# VESC_POWER_SCH.net
KiCad netlist of a schematic drawn in Altium Designer
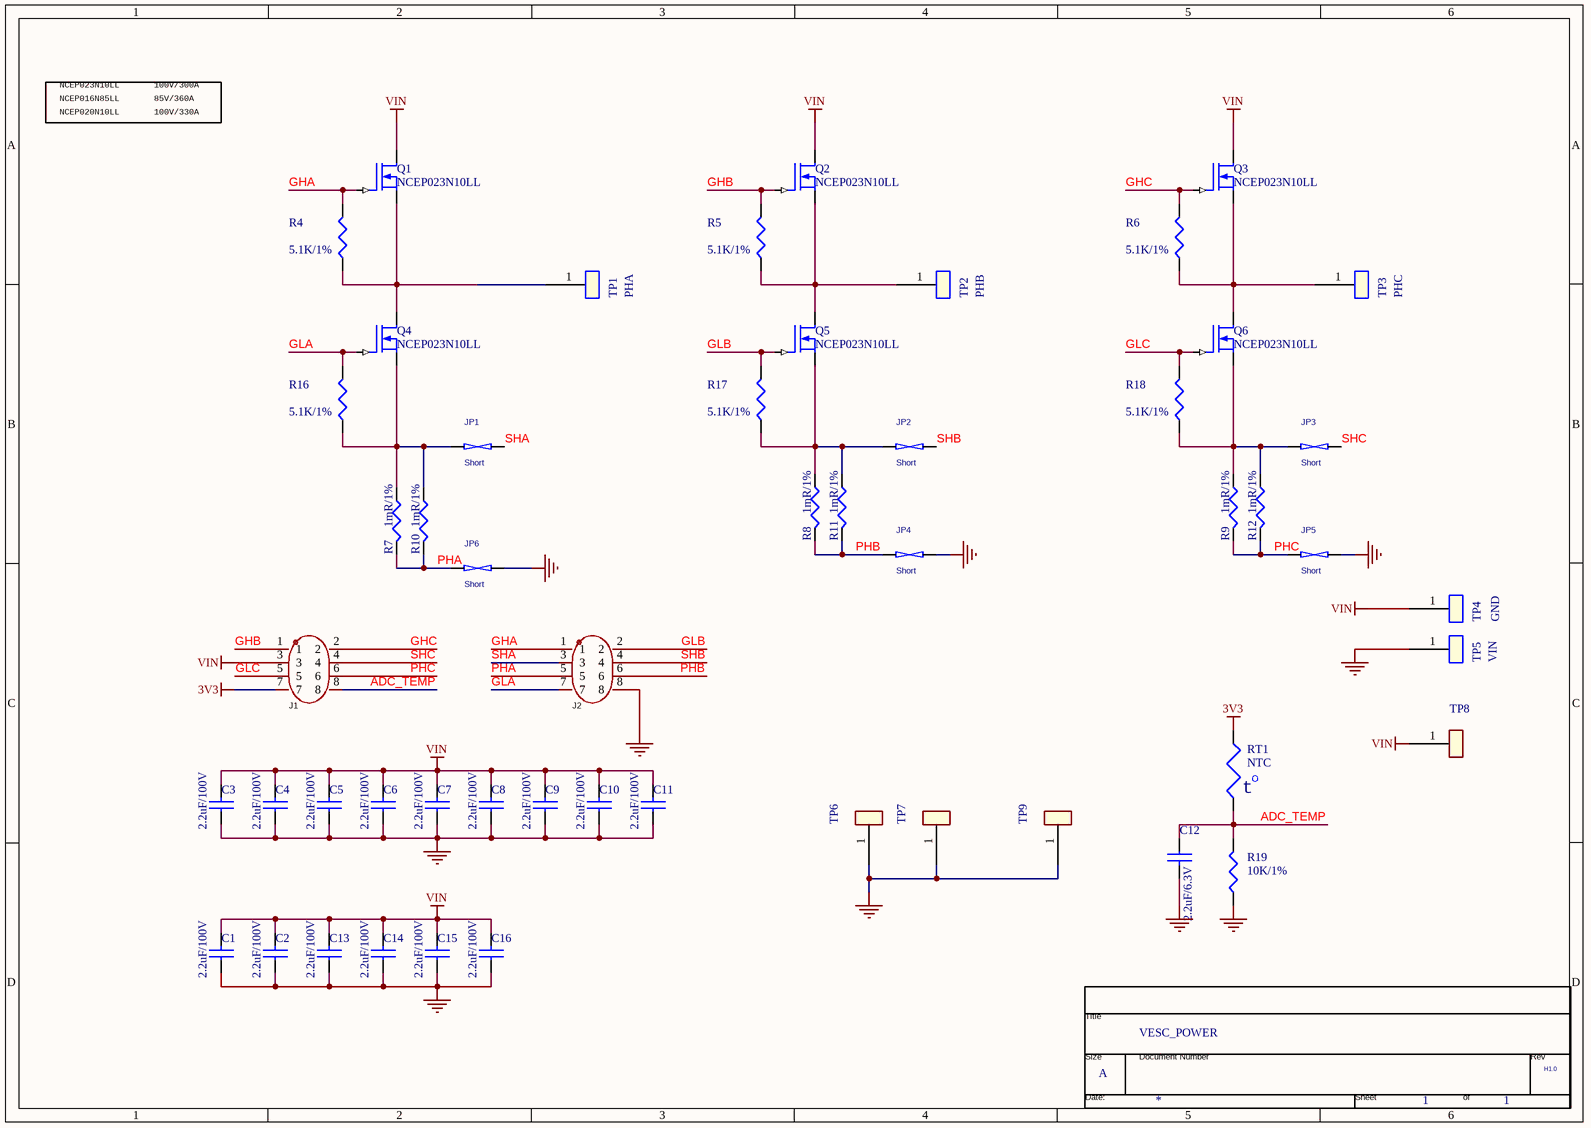
[diagram p0: VESC_POWER_SCH.SchDoc]

(export (version "E")
  (design (tool "Eeschema 10.0.6"))
  (components
    (comp (ref "*")
      (value "TitleBlock0")
      (fields
        (field (name "REVCODE") "H1.0")
        (field (name "TITLE") "VESC_POWER")
        (field (name "PAGE SIZE") "A")
        (field (name "PAGE NUMBER") "1")
        (field (name "PAGE COUNT") "1")
      )
      (libsource (lib "*") (part "TitleBlock0"))
    )
    (comp (ref "C1") (value "2.2uF/100V") (footprint "CAPC3225X230N") (libsource (lib "*") (part "CAP NP")))
    (comp (ref "C2") (value "2.2uF/100V") (footprint "CAPC3225X230N") (libsource (lib "*") (part "CAP NP")))
    (comp (ref "C3") (value "2.2uF/100V") (footprint "CAPC3225X230N") (libsource (lib "*") (part "CAP NP")))
    (comp (ref "C4") (value "2.2uF/100V") (footprint "CAPC3225X230N") (libsource (lib "*") (part "CAP NP")))
    (comp (ref "C5") (value "2.2uF/100V") (footprint "CAPC3225X230N") (libsource (lib "*") (part "CAP NP")))
    (comp (ref "C6") (value "2.2uF/100V") (footprint "CAPC3225X230N") (libsource (lib "*") (part "CAP NP")))
    (comp (ref "C7") (value "2.2uF/100V") (footprint "CAPC3225X230N") (libsource (lib "*") (part "CAP NP")))
    (comp (ref "C8") (value "2.2uF/100V") (footprint "CAPC3225X230N") (libsource (lib "*") (part "CAP NP")))
    (comp (ref "C9") (value "2.2uF/100V") (footprint "CAPC3225X230N") (libsource (lib "*") (part "CAP NP")))
    (comp (ref "C10") (value "2.2uF/100V") (footprint "CAPC3225X230N") (libsource (lib "*") (part "CAP NP")))
    (comp (ref "C11") (value "2.2uF/100V") (footprint "CAPC3225X230N") (libsource (lib "*") (part "CAP NP")))
    (comp (ref "C12") (value "2.2uF/6.3V") (footprint "C0603") (libsource (lib "*") (part "CAP NP")))
    (comp (ref "C13") (value "2.2uF/100V") (footprint "CAPC3225X230N") (libsource (lib "*") (part "CAP NP")))
    (comp (ref "C14") (value "2.2uF/100V") (footprint "CAPC3225X230N") (libsource (lib "*") (part "CAP NP")))
    (comp (ref "C15") (value "2.2uF/100V") (footprint "CAPC3225X230N") (libsource (lib "*") (part "CAP NP")))
    (comp (ref "C16") (value "2.2uF/100V") (footprint "CAPC3225X230N") (libsource (lib "*") (part "CAP NP")))
    (comp (ref "J1")
      (value "X6521WVS-2x04H-C60D74")
      (footprint "HDR-SMD_8P-P1.27-V-M-C2-C4-LS5.3")
      (fields (field (name "MANUFACTURER") "XKB Connection(中国星坤)"))
      (libsource (lib "VESC_POWER_Library") (part "X6521WVS-2x04H-C60D74"))
    )
    (comp (ref "J2")
      (value "X6521WVS-2x04H-C60D74")
      (footprint "HDR-SMD_8P-P1.27-V-M-C2-C4-LS5.3")
      (fields (field (name "MANUFACTURER") "XKB Connection(中国星坤)"))
      (libsource (lib "VESC_POWER_Library") (part "X6521WVS-2x04H-C60D74"))
    )
    (comp (ref "JP1")
      (value "Short")
      (footprint "SHORT")
      (description "2 PIN SHORTED TO CONNECT DIFFERENT NETS")
      (fields (field (name "PART_NUMBER") "TMP-442"))
      (libsource (lib "VESC_POWER_Library") (part "SHORT"))
    )
    (comp (ref "JP2")
      (value "Short")
      (footprint "SHORT")
      (description "2 PIN SHORTED TO CONNECT DIFFERENT NETS")
      (fields (field (name "PART_NUMBER") "TMP-442"))
      (libsource (lib "VESC_POWER_Library") (part "SHORT"))
    )
    (comp (ref "JP3")
      (value "Short")
      (footprint "SHORT")
      (description "2 PIN SHORTED TO CONNECT DIFFERENT NETS")
      (fields (field (name "PART_NUMBER") "TMP-442"))
      (libsource (lib "VESC_POWER_Library") (part "SHORT"))
    )
    (comp (ref "JP4")
      (value "Short")
      (footprint "SHORT")
      (description "2 PIN SHORTED TO CONNECT DIFFERENT NETS")
      (fields (field (name "PART_NUMBER") "TMP-442"))
      (libsource (lib "VESC_POWER_Library") (part "SHORT"))
    )
    (comp (ref "JP5")
      (value "Short")
      (footprint "SHORT")
      (description "2 PIN SHORTED TO CONNECT DIFFERENT NETS")
      (fields (field (name "PART_NUMBER") "TMP-442"))
      (libsource (lib "VESC_POWER_Library") (part "SHORT"))
    )
    (comp (ref "JP6")
      (value "Short")
      (footprint "SHORT")
      (description "2 PIN SHORTED TO CONNECT DIFFERENT NETS")
      (fields (field (name "PART_NUMBER") "TMP-442"))
      (libsource (lib "VESC_POWER_Library") (part "SHORT"))
    )
    (comp (ref "Q1") (value "NCEP023N10LL") (footprint "TOLL") (libsource (lib "*") (part "MOSFET N")))
    (comp (ref "Q2") (value "NCEP023N10LL") (footprint "TOLL") (libsource (lib "*") (part "MOSFET N")))
    (comp (ref "Q3") (value "NCEP023N10LL") (footprint "TOLL") (libsource (lib "*") (part "MOSFET N")))
    (comp (ref "Q4") (value "NCEP023N10LL") (footprint "TOLL") (libsource (lib "*") (part "MOSFET N")))
    (comp (ref "Q5") (value "NCEP023N10LL") (footprint "TOLL") (libsource (lib "*") (part "MOSFET N")))
    (comp (ref "Q6") (value "NCEP023N10LL") (footprint "TOLL") (libsource (lib "*") (part "MOSFET N")))
    (comp (ref "R4") (value "5.1K/1%") (footprint "R0603") (libsource (lib "*") (part "RESISTOR")))
    (comp (ref "R5") (value "5.1K/1%") (footprint "R0603") (libsource (lib "*") (part "RESISTOR")))
    (comp (ref "R6") (value "5.1K/1%") (footprint "R0603") (libsource (lib "*") (part "RESISTOR")))
    (comp (ref "R7") (value "1mR/1%") (footprint "R3920") (libsource (lib "*") (part "RESISTOR")))
    (comp (ref "R8") (value "1mR/1%") (footprint "R3920") (libsource (lib "*") (part "RESISTOR")))
    (comp (ref "R9") (value "1mR/1%") (footprint "R3920") (libsource (lib "*") (part "RESISTOR")))
    (comp (ref "R10") (value "1mR/1%") (footprint "R3920") (libsource (lib "*") (part "RESISTOR")))
    (comp (ref "R11") (value "1mR/1%") (footprint "R3920") (libsource (lib "*") (part "RESISTOR")))
    (comp (ref "R12") (value "1mR/1%") (footprint "R3920") (libsource (lib "*") (part "RESISTOR")))
    (comp (ref "R16") (value "5.1K/1%") (footprint "R0603") (libsource (lib "*") (part "RESISTOR")))
    (comp (ref "R17") (value "5.1K/1%") (footprint "R0603") (libsource (lib "*") (part "RESISTOR")))
    (comp (ref "R18") (value "5.1K/1%") (footprint "R0603") (libsource (lib "*") (part "RESISTOR")))
    (comp (ref "R19") (value "10K/1%") (footprint "R0603") (libsource (lib "*") (part "RESISTOR")))
    (comp (ref "RT1") (value "NTC") (footprint "R0603") (libsource (lib "*") (part "NTC")))
    (comp (ref "TP1") (value "PHA") (footprint "TP_8x8") (libsource (lib "*") (part "TEST POINT")))
    (comp (ref "TP2") (value "PHB") (footprint "TP_8x8") (libsource (lib "*") (part "TEST POINT")))
    (comp (ref "TP3") (value "PHC") (footprint "TP_8x8") (libsource (lib "*") (part "TEST POINT")))
    (comp (ref "TP4") (value "GND") (footprint "TP_8x8") (libsource (lib "*") (part "TEST POINT")))
    (comp (ref "TP5") (value "VIN") (footprint "TP_8x8") (libsource (lib "*") (part "TEST POINT")))
    (comp (ref "TP6")
      (value "TEST POINT")
      (footprint "HOLE-3.2MM_M")
      (libsource (lib "VESC_POWER_Library") (part "TEST POINT"))
    )
    (comp (ref "TP7")
      (value "TEST POINT")
      (footprint "HOLE-3.2MM_M")
      (libsource (lib "VESC_POWER_Library") (part "TEST POINT"))
    )
    (comp (ref "TP8")
      (value "TEST POINT")
      (footprint "HOLE-3.2MM_M")
      (libsource (lib "") (part "TEST POINT_1"))
    )
    (comp (ref "TP9")
      (value "TEST POINT")
      (footprint "HOLE-3.2MM_M")
      (libsource (lib "VESC_POWER_Library") (part "TEST POINT"))
    )
  )
  (nets
    (net (code "1") (name "/ADC_TEMP") (class "Default")
      (node (ref "C12") (pin "1") (pinfunction "1_1") (pintype "passive"))
      (node (ref "J1") (pin "8") (pinfunction "8_8") (pintype "passive"))
      (node (ref "R19") (pin "2") (pinfunction "2_2") (pintype "passive"))
      (node (ref "RT1") (pin "2") (pinfunction "2_2") (pintype "passive"))
    )
    (net (code "2") (name "/GHA") (class "Default")
      (node (ref "J2") (pin "1") (pinfunction "1_1") (pintype "passive"))
      (node (ref "Q1") (pin "1") (pinfunction "GATE_1") (pintype "input"))
      (node (ref "R4") (pin "2") (pinfunction "2_2") (pintype "passive"))
    )
    (net (code "3") (name "/GHB") (class "Default")
      (node (ref "J1") (pin "1") (pinfunction "1_1") (pintype "passive"))
      (node (ref "Q2") (pin "1") (pinfunction "GATE_1") (pintype "input"))
      (node (ref "R5") (pin "2") (pinfunction "2_2") (pintype "passive"))
    )
    (net (code "4") (name "/GHC") (class "Default")
      (node (ref "J1") (pin "2") (pinfunction "2_2") (pintype "passive"))
      (node (ref "Q3") (pin "1") (pinfunction "GATE_1") (pintype "input"))
      (node (ref "R6") (pin "2") (pinfunction "2_2") (pintype "passive"))
    )
    (net (code "5") (name "/GLA") (class "Default")
      (node (ref "J2") (pin "7") (pinfunction "7_7") (pintype "passive"))
      (node (ref "Q4") (pin "1") (pinfunction "GATE_1") (pintype "input"))
      (node (ref "R16") (pin "2") (pinfunction "2_2") (pintype "passive"))
    )
    (net (code "6") (name "/GLB") (class "Default")
      (node (ref "J2") (pin "2") (pinfunction "2_2") (pintype "passive"))
      (node (ref "Q5") (pin "1") (pinfunction "GATE_1") (pintype "input"))
      (node (ref "R17") (pin "2") (pinfunction "2_2") (pintype "passive"))
    )
    (net (code "7") (name "/GLC") (class "Default")
      (node (ref "J1") (pin "5") (pinfunction "5_5") (pintype "passive"))
      (node (ref "Q6") (pin "1") (pinfunction "GATE_1") (pintype "input"))
      (node (ref "R18") (pin "2") (pinfunction "2_2") (pintype "passive"))
    )
    (net (code "8") (name "/PHA") (class "Default")
      (node (ref "J2") (pin "5") (pinfunction "5_5") (pintype "passive"))
      (node (ref "JP6") (pin "1") (pinfunction "1_1") (pintype "passive"))
      (node (ref "R10") (pin "2") (pinfunction "2_2") (pintype "passive"))
      (node (ref "R7") (pin "2") (pinfunction "2_2") (pintype "passive"))
    )
    (net (code "9") (name "/PHB") (class "Default")
      (node (ref "J2") (pin "6") (pinfunction "6_6") (pintype "passive"))
      (node (ref "JP4") (pin "1") (pinfunction "1_1") (pintype "passive"))
      (node (ref "R11") (pin "2") (pinfunction "2_2") (pintype "passive"))
      (node (ref "R8") (pin "2") (pinfunction "2_2") (pintype "passive"))
    )
    (net (code "10") (name "/PHC") (class "Default")
      (node (ref "J1") (pin "6") (pinfunction "6_6") (pintype "passive"))
      (node (ref "JP5") (pin "1") (pinfunction "1_1") (pintype "passive"))
      (node (ref "R12") (pin "2") (pinfunction "2_2") (pintype "passive"))
      (node (ref "R9") (pin "2") (pinfunction "2_2") (pintype "passive"))
    )
    (net (code "11") (name "/SHA") (class "Default")
      (node (ref "J2") (pin "3") (pinfunction "3_3") (pintype "passive"))
      (node (ref "JP1") (pin "2") (pinfunction "2_2") (pintype "passive"))
    )
    (net (code "12") (name "/SHB") (class "Default")
      (node (ref "J2") (pin "4") (pinfunction "4_4") (pintype "passive"))
      (node (ref "JP2") (pin "2") (pinfunction "2_2") (pintype "passive"))
    )
    (net (code "13") (name "/SHC") (class "Default")
      (node (ref "J1") (pin "4") (pinfunction "4_4") (pintype "passive"))
      (node (ref "JP3") (pin "2") (pinfunction "2_2") (pintype "passive"))
    )
    (net (code "14") (name "3V3") (class "Default")
      (node (ref "J1") (pin "7") (pinfunction "7_7") (pintype "passive"))
      (node (ref "RT1") (pin "1") (pinfunction "1_1") (pintype "passive"))
    )
    (net (code "15") (name "GND") (class "Default")
      (node (ref "C1") (pin "1") (pinfunction "1_1") (pintype "passive"))
      (node (ref "C10") (pin "1") (pinfunction "1_1") (pintype "passive"))
      (node (ref "C11") (pin "1") (pinfunction "1_1") (pintype "passive"))
      (node (ref "C12") (pin "2") (pinfunction "2_2") (pintype "passive"))
      (node (ref "C13") (pin "1") (pinfunction "1_1") (pintype "passive"))
      (node (ref "C14") (pin "1") (pinfunction "1_1") (pintype "passive"))
      (node (ref "C15") (pin "1") (pinfunction "1_1") (pintype "passive"))
      (node (ref "C16") (pin "1") (pinfunction "1_1") (pintype "passive"))
      (node (ref "C2") (pin "1") (pinfunction "1_1") (pintype "passive"))
      (node (ref "C3") (pin "1") (pinfunction "1_1") (pintype "passive"))
      (node (ref "C4") (pin "1") (pinfunction "1_1") (pintype "passive"))
      (node (ref "C5") (pin "1") (pinfunction "1_1") (pintype "passive"))
      (node (ref "C6") (pin "1") (pinfunction "1_1") (pintype "passive"))
      (node (ref "C7") (pin "1") (pinfunction "1_1") (pintype "passive"))
      (node (ref "C8") (pin "1") (pinfunction "1_1") (pintype "passive"))
      (node (ref "C9") (pin "1") (pinfunction "1_1") (pintype "passive"))
      (node (ref "J2") (pin "8") (pinfunction "8_8") (pintype "passive"))
      (node (ref "JP4") (pin "2") (pinfunction "2_2") (pintype "passive"))
      (node (ref "JP5") (pin "2") (pinfunction "2_2") (pintype "passive"))
      (node (ref "JP6") (pin "2") (pinfunction "2_2") (pintype "passive"))
      (node (ref "R19") (pin "1") (pinfunction "1_1") (pintype "passive"))
      (node (ref "TP5") (pin "1") (pinfunction "1_1") (pintype "passive"))
      (node (ref "TP6") (pin "1") (pinfunction "1_1") (pintype "passive"))
      (node (ref "TP7") (pin "1") (pinfunction "1_1") (pintype "passive"))
      (node (ref "TP9") (pin "1") (pinfunction "1_1") (pintype "passive"))
    )
    (net (code "16") (name "Net-(Q1-SOURCE)") (class "Default")
      (node (ref "Q1") (pin "3") (pinfunction "SOURCE_3") (pintype "passive"))
      (node (ref "Q4") (pin "2") (pinfunction "DRAIN_2") (pintype "passive"))
      (node (ref "R4") (pin "1") (pinfunction "1_1") (pintype "passive"))
      (node (ref "TP1") (pin "1") (pinfunction "1_1") (pintype "passive"))
    )
    (net (code "17") (name "Net-(Q2-SOURCE)") (class "Default")
      (node (ref "Q2") (pin "3") (pinfunction "SOURCE_3") (pintype "passive"))
      (node (ref "Q5") (pin "2") (pinfunction "DRAIN_2") (pintype "passive"))
      (node (ref "R5") (pin "1") (pinfunction "1_1") (pintype "passive"))
      (node (ref "TP2") (pin "1") (pinfunction "1_1") (pintype "passive"))
    )
    (net (code "18") (name "Net-(Q3-SOURCE)") (class "Default")
      (node (ref "Q3") (pin "3") (pinfunction "SOURCE_3") (pintype "passive"))
      (node (ref "Q6") (pin "2") (pinfunction "DRAIN_2") (pintype "passive"))
      (node (ref "R6") (pin "1") (pinfunction "1_1") (pintype "passive"))
      (node (ref "TP3") (pin "1") (pinfunction "1_1") (pintype "passive"))
    )
    (net (code "19") (name "Net-(Q4-SOURCE)") (class "Default")
      (node (ref "JP1") (pin "1") (pinfunction "1_1") (pintype "passive"))
      (node (ref "Q4") (pin "3") (pinfunction "SOURCE_3") (pintype "passive"))
      (node (ref "R10") (pin "1") (pinfunction "1_1") (pintype "passive"))
      (node (ref "R16") (pin "1") (pinfunction "1_1") (pintype "passive"))
      (node (ref "R7") (pin "1") (pinfunction "1_1") (pintype "passive"))
    )
    (net (code "20") (name "Net-(Q5-SOURCE)") (class "Default")
      (node (ref "JP2") (pin "1") (pinfunction "1_1") (pintype "passive"))
      (node (ref "Q5") (pin "3") (pinfunction "SOURCE_3") (pintype "passive"))
      (node (ref "R11") (pin "1") (pinfunction "1_1") (pintype "passive"))
      (node (ref "R17") (pin "1") (pinfunction "1_1") (pintype "passive"))
      (node (ref "R8") (pin "1") (pinfunction "1_1") (pintype "passive"))
    )
    (net (code "21") (name "Net-(Q6-SOURCE)") (class "Default")
      (node (ref "JP3") (pin "1") (pinfunction "1_1") (pintype "passive"))
      (node (ref "Q6") (pin "3") (pinfunction "SOURCE_3") (pintype "passive"))
      (node (ref "R12") (pin "1") (pinfunction "1_1") (pintype "passive"))
      (node (ref "R18") (pin "1") (pinfunction "1_1") (pintype "passive"))
      (node (ref "R9") (pin "1") (pinfunction "1_1") (pintype "passive"))
    )
    (net (code "22") (name "VIN") (class "Default")
      (node (ref "C1") (pin "2") (pinfunction "2_2") (pintype "passive"))
      (node (ref "C10") (pin "2") (pinfunction "2_2") (pintype "passive"))
      (node (ref "C11") (pin "2") (pinfunction "2_2") (pintype "passive"))
      (node (ref "C13") (pin "2") (pinfunction "2_2") (pintype "passive"))
      (node (ref "C14") (pin "2") (pinfunction "2_2") (pintype "passive"))
      (node (ref "C15") (pin "2") (pinfunction "2_2") (pintype "passive"))
      (node (ref "C16") (pin "2") (pinfunction "2_2") (pintype "passive"))
      (node (ref "C2") (pin "2") (pinfunction "2_2") (pintype "passive"))
      (node (ref "C3") (pin "2") (pinfunction "2_2") (pintype "passive"))
      (node (ref "C4") (pin "2") (pinfunction "2_2") (pintype "passive"))
      (node (ref "C5") (pin "2") (pinfunction "2_2") (pintype "passive"))
      (node (ref "C6") (pin "2") (pinfunction "2_2") (pintype "passive"))
      (node (ref "C7") (pin "2") (pinfunction "2_2") (pintype "passive"))
      (node (ref "C8") (pin "2") (pinfunction "2_2") (pintype "passive"))
      (node (ref "C9") (pin "2") (pinfunction "2_2") (pintype "passive"))
      (node (ref "J1") (pin "3") (pinfunction "3_3") (pintype "passive"))
      (node (ref "Q1") (pin "2") (pinfunction "DRAIN_2") (pintype "passive"))
      (node (ref "Q2") (pin "2") (pinfunction "DRAIN_2") (pintype "passive"))
      (node (ref "Q3") (pin "2") (pinfunction "DRAIN_2") (pintype "passive"))
      (node (ref "TP4") (pin "1") (pinfunction "1_1") (pintype "passive"))
      (node (ref "TP8") (pin "1") (pinfunction "1_1") (pintype "passive"))
    )
  )
)
